# 555-timer-CD4017BE.net
KiCad netlist of a schematic drawn in EasyEDA Pro
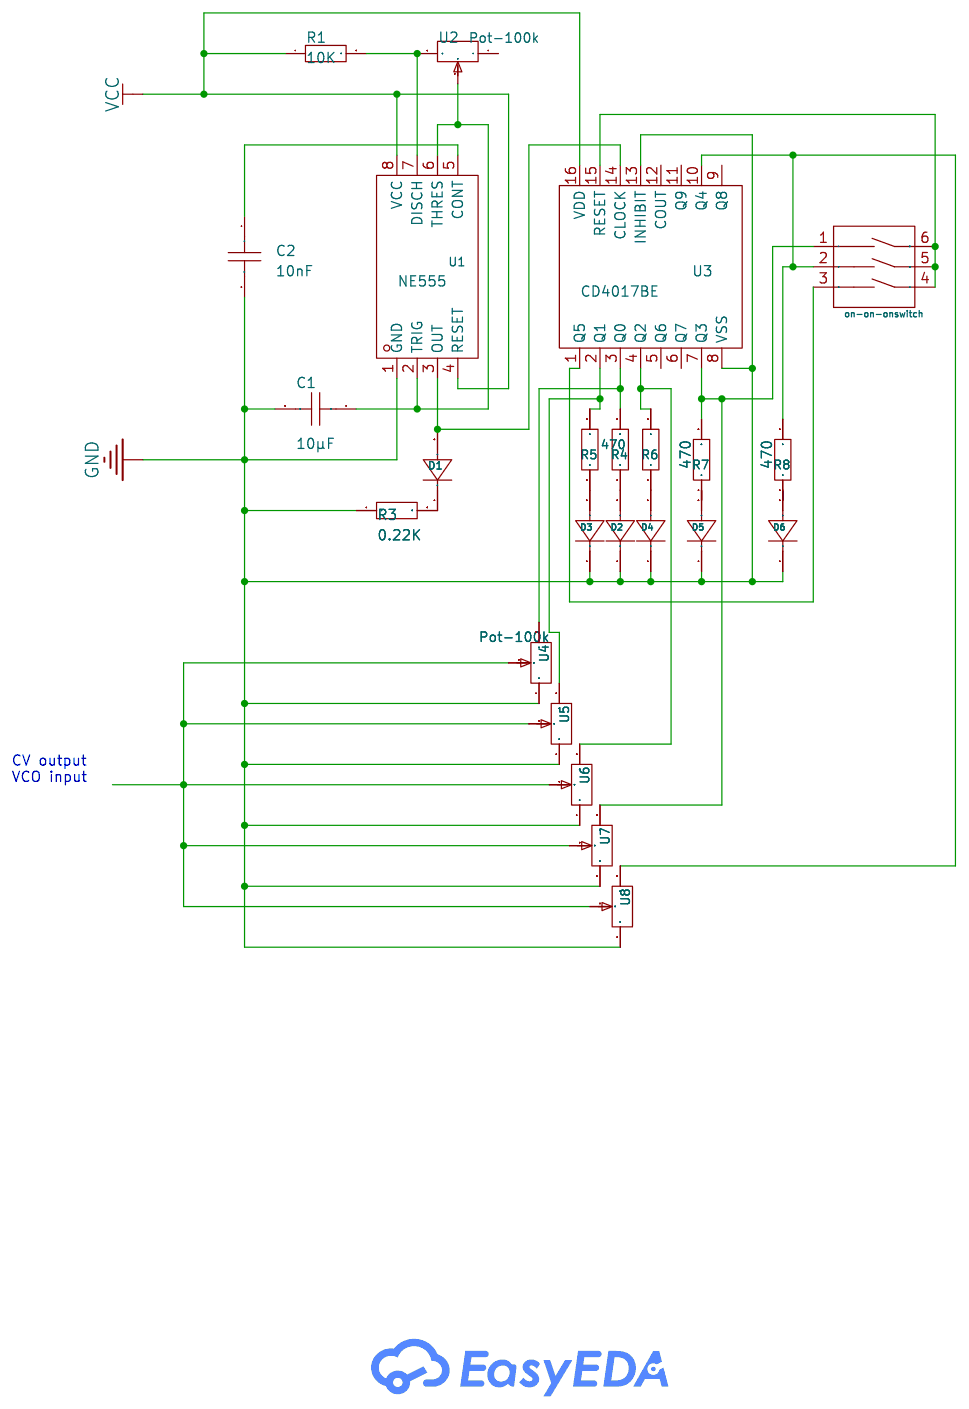
[diagram p0: schematic sheet]

(export (version "E")
  (design (tool "Eeschema 10.0.6"))
  (components
    (comp (ref "C1")
      (value "10µF")
      (footprint "easyedapro:C0603")
      (libsource (lib "easyedapro") (part "CAP"))
    )
    (comp (ref "C2")
      (value "10nF")
      (footprint "easyedapro:C0603")
      (libsource (lib "easyedapro") (part "CAP"))
    )
    (comp (ref "D1")
      (value "~")
      (footprint "easyedapro:SMA_L4.4-W2.8-LS5.4-RD")
      (libsource (lib "easyedapro") (part "D_1N4007"))
    )
    (comp (ref "D2")
      (value "~")
      (footprint "easyedapro:SMA_L4.4-W2.8-LS5.4-RD")
      (libsource (lib "easyedapro") (part "D_1N4007"))
    )
    (comp (ref "D3")
      (value "~")
      (footprint "easyedapro:SMA_L4.4-W2.8-LS5.4-RD")
      (libsource (lib "easyedapro") (part "D_1N4007"))
    )
    (comp (ref "D4")
      (value "~")
      (footprint "easyedapro:SMA_L4.4-W2.8-LS5.4-RD")
      (libsource (lib "easyedapro") (part "D_1N4007"))
    )
    (comp (ref "D5")
      (value "~")
      (footprint "easyedapro:SMA_L4.4-W2.8-LS5.4-RD")
      (libsource (lib "easyedapro") (part "D_1N4007"))
    )
    (comp (ref "D6")
      (value "~")
      (footprint "easyedapro:SMA_L4.4-W2.8-LS5.4-RD")
      (libsource (lib "easyedapro") (part "D_1N4007"))
    )
    (comp (ref "on-on-onswitch")
      (value "ATE2D-2M3-10-Z")
      (footprint "easyedapro:SW-TH_ATE2D-2M3-10-Z")
      (fields (field (name "Manufacturer") "NIDEC(尼得科)"))
      (libsource (lib "easyedapro") (part "ATE2D-2M3-10-Z"))
    )
    (comp (ref "R1") (value "10K") (footprint "easyedapro:R0603") (libsource (lib "easyedapro") (part "Res")))
    (comp (ref "R3")
      (value "0.22K")
      (footprint "easyedapro:R0603")
      (libsource (lib "easyedapro") (part "Res"))
    )
    (comp (ref "R4") (value "470") (footprint "easyedapro:R0603") (libsource (lib "easyedapro") (part "Res")))
    (comp (ref "R5") (value "470") (footprint "easyedapro:R0603") (libsource (lib "easyedapro") (part "Res")))
    (comp (ref "R6") (value "470") (footprint "easyedapro:R0603") (libsource (lib "easyedapro") (part "Res")))
    (comp (ref "R7") (value "470") (footprint "easyedapro:R0603") (libsource (lib "easyedapro") (part "Res")))
    (comp (ref "R8") (value "470") (footprint "easyedapro:R0603") (libsource (lib "easyedapro") (part "Res")))
    (comp (ref "U1")
      (value "NE555")
      (footprint "easyedapro:SOIC-8_L4.9-W3.9-P1.27-LS6.0-BL")
      (fields (field (name "Manufacturer") "IDCHIP(英锐芯)"))
      (libsource (lib "easyedapro") (part "NE555_C5125085"))
    )
    (comp (ref "U2")
      (value "Pot-100k")
      (footprint "easyedapro:RES-ADJ-SMD_VG039NCH")
      (libsource (lib "easyedapro") (part "3*3POTENTIOMETER-10KΩ20%"))
    )
    (comp (ref "U3")
      (value "CD4017BE")
      (footprint "easyedapro:DIP-16_L19.2-W6.6-P2.54-LS7.6-BL")
      (fields (field (name "Manufacturer") "HGSEMI(华冠)"))
      (libsource (lib "easyedapro") (part "CD4017BE_C507168"))
    )
    (comp (ref "U4")
      (value "Pot-100k")
      (footprint "easyedapro:RES-ADJ-SMD_VG039NCH")
      (libsource (lib "easyedapro") (part "3*3POTENTIOMETER-10KΩ20%"))
    )
    (comp (ref "U5")
      (value "Pot-100k")
      (footprint "easyedapro:RES-ADJ-SMD_VG039NCH")
      (libsource (lib "easyedapro") (part "3*3POTENTIOMETER-10KΩ20%"))
    )
    (comp (ref "U6")
      (value "Pot-100k")
      (footprint "easyedapro:RES-ADJ-SMD_VG039NCH")
      (libsource (lib "easyedapro") (part "3*3POTENTIOMETER-10KΩ20%"))
    )
    (comp (ref "U7")
      (value "Pot-100k")
      (footprint "easyedapro:RES-ADJ-SMD_VG039NCH")
      (libsource (lib "easyedapro") (part "3*3POTENTIOMETER-10KΩ20%"))
    )
    (comp (ref "U8")
      (value "Pot-100k")
      (footprint "easyedapro:RES-ADJ-SMD_VG039NCH")
      (libsource (lib "easyedapro") (part "3*3POTENTIOMETER-10KΩ20%"))
    )
  )
  (nets
    (net (code "1") (name "GND") (class "Default")
      (node (ref "C1") (pin "2") (pinfunction "2_2") (pintype "input"))
      (node (ref "C2") (pin "2") (pinfunction "2_2") (pintype "input"))
      (node (ref "D2") (pin "1") (pinfunction "K_1") (pintype "input"))
      (node (ref "D3") (pin "1") (pinfunction "K_1") (pintype "input"))
      (node (ref "D4") (pin "1") (pinfunction "K_1") (pintype "input"))
      (node (ref "D5") (pin "1") (pinfunction "K_1") (pintype "input"))
      (node (ref "D6") (pin "1") (pinfunction "K_1") (pintype "input"))
      (node (ref "R3") (pin "1") (pinfunction "1_1") (pintype "input"))
      (node (ref "U1") (pin "1") (pinfunction "GND_1") (pintype "input"))
      (node (ref "U3") (pin "13") (pinfunction "INHIBIT_13") (pintype "unspecified"))
      (node (ref "U3") (pin "8") (pinfunction "VSS_8") (pintype "unspecified"))
      (node (ref "U4") (pin "1") (pinfunction "1_1") (pintype "input"))
      (node (ref "U5") (pin "1") (pinfunction "1_1") (pintype "input"))
      (node (ref "U6") (pin "1") (pinfunction "1_1") (pintype "input"))
      (node (ref "U7") (pin "1") (pinfunction "1_1") (pintype "input"))
      (node (ref "U8") (pin "1") (pinfunction "1_1") (pintype "input"))
    )
    (net (code "2") (name "Net-(D1-A)") (class "Default")
      (node (ref "D1") (pin "2") (pinfunction "A_2") (pintype "input"))
      (node (ref "U1") (pin "3") (pinfunction "OUT_3") (pintype "input"))
      (node (ref "U3") (pin "14") (pinfunction "CLOCK_14") (pintype "unspecified"))
    )
    (net (code "3") (name "Net-(D1-K)") (class "Default")
      (node (ref "D1") (pin "1") (pinfunction "K_1") (pintype "input"))
      (node (ref "R3") (pin "2") (pinfunction "2_2") (pintype "input"))
    )
    (net (code "4") (name "Net-(D2-A)") (class "Default")
      (node (ref "D2") (pin "2") (pinfunction "A_2") (pintype "input"))
      (node (ref "R4") (pin "1") (pinfunction "1_1") (pintype "input"))
    )
    (net (code "5") (name "Net-(D3-A)") (class "Default")
      (node (ref "D3") (pin "2") (pinfunction "A_2") (pintype "input"))
      (node (ref "R5") (pin "1") (pinfunction "1_1") (pintype "input"))
    )
    (net (code "6") (name "Net-(D4-A)") (class "Default")
      (node (ref "D4") (pin "2") (pinfunction "A_2") (pintype "input"))
      (node (ref "R6") (pin "1") (pinfunction "1_1") (pintype "input"))
    )
    (net (code "7") (name "Net-(D5-A)") (class "Default")
      (node (ref "D5") (pin "2") (pinfunction "A_2") (pintype "input"))
      (node (ref "R7") (pin "1") (pinfunction "1_1") (pintype "input"))
    )
    (net (code "8") (name "Net-(D6-A)") (class "Default")
      (node (ref "D6") (pin "2") (pinfunction "A_2") (pintype "input"))
      (node (ref "R8") (pin "1") (pinfunction "1_1") (pintype "input"))
    )
    (net (code "9") (name "Net-(U1-CONT)") (class "Default")
      (node (ref "C2") (pin "1") (pinfunction "1_1") (pintype "input"))
      (node (ref "U1") (pin "5") (pinfunction "CONT_5") (pintype "input"))
    )
    (net (code "10") (name "Net-(U1-DISCH)") (class "Default")
      (node (ref "R1") (pin "2") (pinfunction "2_2") (pintype "input"))
      (node (ref "U1") (pin "7") (pinfunction "DISCH_7") (pintype "input"))
      (node (ref "U2") (pin "3") (pinfunction "3_3") (pintype "input"))
    )
    (net (code "11") (name "Net-(U1-THRES)") (class "Default")
      (node (ref "C1") (pin "1") (pinfunction "1_1") (pintype "input"))
      (node (ref "U1") (pin "2") (pinfunction "TRIG_2") (pintype "input"))
      (node (ref "U1") (pin "6") (pinfunction "THRES_6") (pintype "input"))
      (node (ref "U2") (pin "2") (pinfunction "2_2") (pintype "input"))
    )
    (net (code "12") (name "Net-(U3-Q0)") (class "Default")
      (node (ref "R4") (pin "2") (pinfunction "2_2") (pintype "input"))
      (node (ref "U3") (pin "3") (pinfunction "Q0_3") (pintype "unspecified"))
      (node (ref "U4") (pin "3") (pinfunction "3_3") (pintype "input"))
    )
    (net (code "13") (name "Net-(U3-Q1)") (class "Default")
      (node (ref "R5") (pin "2") (pinfunction "2_2") (pintype "input"))
      (node (ref "U3") (pin "2") (pinfunction "Q1_2") (pintype "unspecified"))
      (node (ref "U5") (pin "3") (pinfunction "3_3") (pintype "input"))
    )
    (net (code "14") (name "Net-(U3-Q2)") (class "Default")
      (node (ref "R6") (pin "2") (pinfunction "2_2") (pintype "input"))
      (node (ref "U3") (pin "4") (pinfunction "Q2_4") (pintype "unspecified"))
      (node (ref "U6") (pin "3") (pinfunction "3_3") (pintype "input"))
    )
    (net (code "15") (name "Net-(U3-Q3)") (class "Default")
      (node (ref "R7") (pin "2") (pinfunction "2_2") (pintype "input"))
      (node (ref "U3") (pin "7") (pinfunction "Q3_7") (pintype "unspecified"))
      (node (ref "U7") (pin "3") (pinfunction "3_3") (pintype "input"))
      (node (ref "on-on-onswitch") (pin "1") (pinfunction "1_1") (pintype "unspecified"))
    )
    (net (code "16") (name "Net-(U3-Q4)") (class "Default")
      (node (ref "R8") (pin "2") (pinfunction "2_2") (pintype "input"))
      (node (ref "U3") (pin "10") (pinfunction "Q4_10") (pintype "unspecified"))
      (node (ref "U8") (pin "3") (pinfunction "3_3") (pintype "input"))
      (node (ref "on-on-onswitch") (pin "2") (pinfunction "2_2") (pintype "unspecified"))
    )
    (net (code "17") (name "Net-(U3-Q5)") (class "Default")
      (node (ref "U3") (pin "1") (pinfunction "Q5_1") (pintype "unspecified"))
      (node (ref "on-on-onswitch") (pin "3") (pinfunction "3_3") (pintype "unspecified"))
    )
    (net (code "18") (name "Net-(U3-RESET)") (class "Default")
      (node (ref "U3") (pin "15") (pinfunction "RESET_15") (pintype "unspecified"))
      (node (ref "on-on-onswitch") (pin "4") (pinfunction "4_4") (pintype "unspecified"))
      (node (ref "on-on-onswitch") (pin "5") (pinfunction "5_5") (pintype "unspecified"))
      (node (ref "on-on-onswitch") (pin "6") (pinfunction "6_6") (pintype "unspecified"))
    )
    (net (code "19") (name "Net-(U4-Pad2)") (class "Default")
      (node (ref "U4") (pin "2") (pinfunction "2_2") (pintype "input"))
      (node (ref "U5") (pin "2") (pinfunction "2_2") (pintype "input"))
      (node (ref "U6") (pin "2") (pinfunction "2_2") (pintype "input"))
      (node (ref "U7") (pin "2") (pinfunction "2_2") (pintype "input"))
      (node (ref "U8") (pin "2") (pinfunction "2_2") (pintype "input"))
    )
    (net (code "20") (name "VCC") (class "Default")
      (node (ref "R1") (pin "1") (pinfunction "1_1") (pintype "input"))
      (node (ref "U1") (pin "4") (pinfunction "RESET_4") (pintype "input"))
      (node (ref "U1") (pin "8") (pinfunction "VCC_8") (pintype "input"))
      (node (ref "U3") (pin "16") (pinfunction "VDD_16") (pintype "unspecified"))
    )
    (net (code "21") (name "unconnected-(U2-Pad1)") (class "Default")
      (node (ref "U2") (pin "1") (pinfunction "1_1") (pintype "input"))
    )
    (net (code "22") (name "unconnected-(U3-COUT-Pad12)") (class "Default")
      (node (ref "U3") (pin "12") (pinfunction "COUT_12") (pintype "unspecified"))
    )
    (net (code "23") (name "unconnected-(U3-Q6-Pad5)") (class "Default")
      (node (ref "U3") (pin "5") (pinfunction "Q6_5") (pintype "unspecified"))
    )
    (net (code "24") (name "unconnected-(U3-Q7-Pad6)") (class "Default")
      (node (ref "U3") (pin "6") (pinfunction "Q7_6") (pintype "unspecified"))
    )
    (net (code "25") (name "unconnected-(U3-Q8-Pad9)") (class "Default")
      (node (ref "U3") (pin "9") (pinfunction "Q8_9") (pintype "unspecified"))
    )
    (net (code "26") (name "unconnected-(U3-Q9-Pad11)") (class "Default")
      (node (ref "U3") (pin "11") (pinfunction "Q9_11") (pintype "unspecified"))
    )
  )
)
